# canayaz2560mega.net
KiCad netlist of a schematic drawn in EAGLE
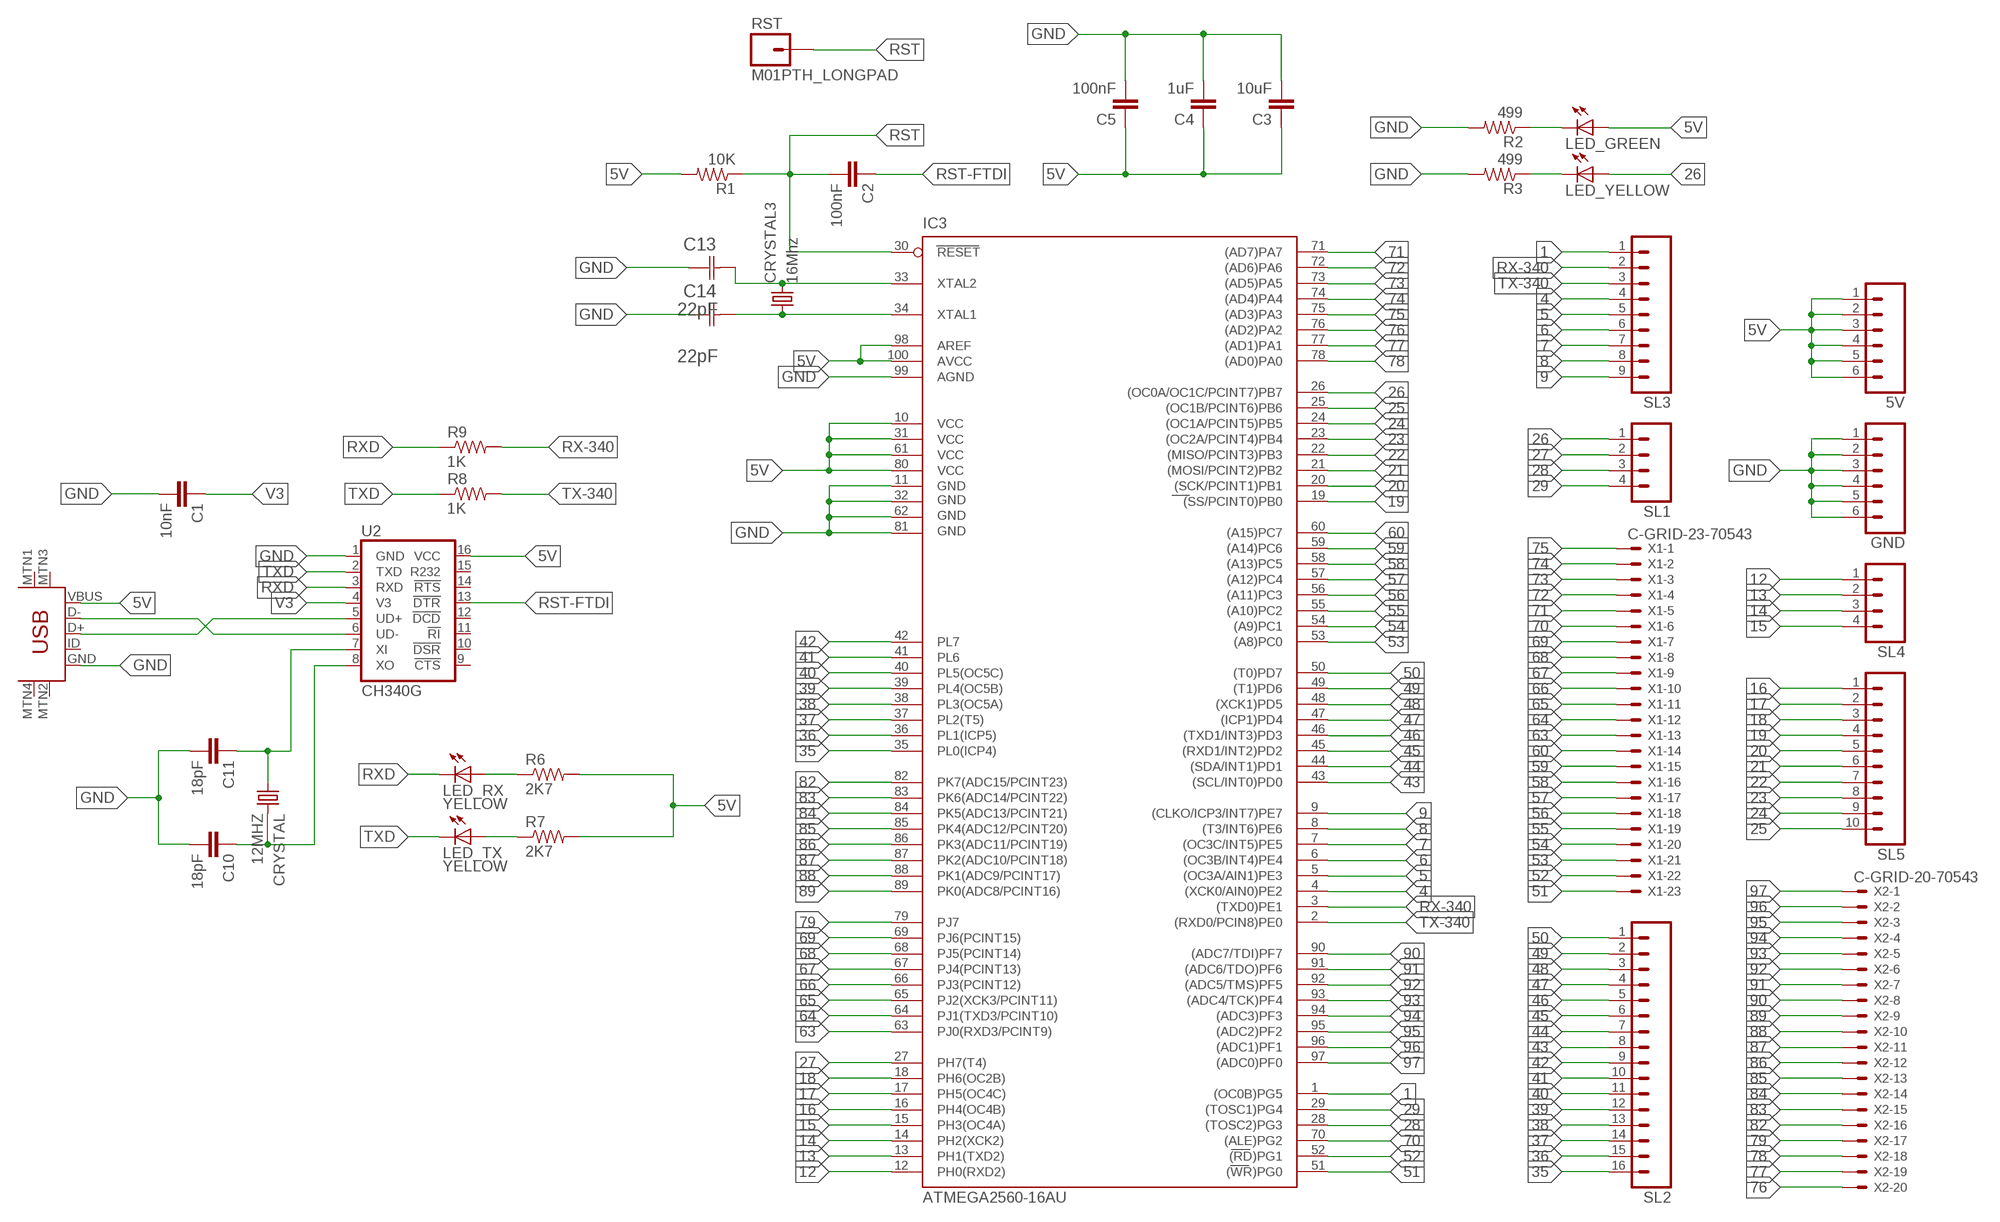
[diagram p0: schematic, sheet 1]

(export (version "E")
  (design (tool "Eeschema 10.0.6"))
  (components
    (comp (ref "5V")
      (value "M06")
      (footprint "eagle-import:06P")
      (libsource (lib "eagle-import") (part "M06"))
    )
    (comp (ref "C1")
      (value "10nF")
      (footprint "eagle-import:1206")
      (libsource (lib "eagle-import") (part "CAP1206"))
    )
    (comp (ref "C2")
      (value "100nF")
      (footprint "eagle-import:1206")
      (libsource (lib "eagle-import") (part "CAP1206"))
    )
    (comp (ref "C3")
      (value "10uF")
      (footprint "eagle-import:1206")
      (libsource (lib "eagle-import") (part "CAP1206"))
    )
    (comp (ref "C4")
      (value "1uF")
      (footprint "eagle-import:1206")
      (libsource (lib "eagle-import") (part "CAP1206"))
    )
    (comp (ref "C5")
      (value "100nF")
      (footprint "eagle-import:1206")
      (libsource (lib "eagle-import") (part "CAP1206"))
    )
    (comp (ref "C10")
      (value "18pF")
      (footprint "eagle-import:1206")
      (libsource (lib "eagle-import") (part "CAP1206"))
    )
    (comp (ref "C11")
      (value "18pF")
      (footprint "eagle-import:1206")
      (libsource (lib "eagle-import") (part "CAP1206"))
    )
    (comp (ref "C13")
      (value "22pF")
      (footprint "eagle-import:CAPC3216X178N")
      (fields (field (name "MPN") "0612ZC225MAT2A") (field (name "TOLERANCE") "±20%"))
      (libsource (lib "eagle-import") (part "0612ZC225MAT2A"))
    )
    (comp (ref "C14")
      (value "22pF")
      (footprint "eagle-import:CAPC3216X178N")
      (fields (field (name "MPN") "0612ZC225MAT2A") (field (name "TOLERANCE") "±20%"))
      (libsource (lib "eagle-import") (part "0612ZC225MAT2A"))
    )
    (comp (ref "CRYSTAL")
      (value "12MHZ")
      (footprint "eagle-import:CSM-7X-DU")
      (libsource (lib "eagle-import") (part "flight_controller.lbr01_FAB_Hello_CSM-7X-DU"))
    )
    (comp (ref "CRYSTAL3")
      (value "16Mhz")
      (footprint "eagle-import:CSM-7X-DU")
      (libsource (lib "eagle-import") (part "CSM-7X-DU"))
    )
    (comp (ref "GND")
      (value "M06")
      (footprint "eagle-import:06P")
      (libsource (lib "eagle-import") (part "M06"))
    )
    (comp (ref "IC3")
      (value "ATMEGA2560-16AU")
      (footprint "eagle-import:TQFP100")
      (libsource (lib "eagle-import") (part "ATMEGAAU1280-16"))
    )
    (comp (ref "LED_GREEN")
      (value "LED1206")
      (footprint "eagle-import:1206")
      (libsource (lib "eagle-import") (part "LED1206"))
    )
    (comp (ref "LED_RX")
      (value "YELLOW")
      (footprint "eagle-import:LED1206")
      (libsource (lib "eagle-import") (part "LED"))
    )
    (comp (ref "LED_TX")
      (value "YELLOW")
      (footprint "eagle-import:LED1206")
      (libsource (lib "eagle-import") (part "LED"))
    )
    (comp (ref "LED_YELLOW")
      (value "LED1206")
      (footprint "eagle-import:1206")
      (libsource (lib "eagle-import") (part "LED1206"))
    )
    (comp (ref "R1")
      (value "10K")
      (footprint "eagle-import:R1206")
      (libsource (lib "eagle-import") (part "RES-US1206"))
    )
    (comp (ref "R2")
      (value "499")
      (footprint "eagle-import:1206")
      (libsource (lib "eagle-import") (part "RESISTOR1206"))
    )
    (comp (ref "R3")
      (value "499")
      (footprint "eagle-import:1206")
      (libsource (lib "eagle-import") (part "RESISTOR1206"))
    )
    (comp (ref "R6")
      (value "2K7")
      (footprint "eagle-import:R1206")
      (libsource (lib "eagle-import") (part "RES-US1206"))
    )
    (comp (ref "R7")
      (value "2K7")
      (footprint "eagle-import:R1206")
      (libsource (lib "eagle-import") (part "RES-US1206"))
    )
    (comp (ref "R8")
      (value "1K")
      (footprint "eagle-import:R1206")
      (libsource (lib "eagle-import") (part "RES-US1206"))
    )
    (comp (ref "R9")
      (value "1K")
      (footprint "eagle-import:R1206")
      (libsource (lib "eagle-import") (part "RES-US1206"))
    )
    (comp (ref "RST")
      (value "M01PTH_LONGPAD")
      (footprint "eagle-import:1X01_LONGPAD")
      (libsource (lib "eagle-import") (part "M01PTH_LONGPAD"))
    )
    (comp (ref "SL1")
      (value "M04")
      (footprint "eagle-import:04P")
      (libsource (lib "eagle-import") (part "M04"))
    )
    (comp (ref "SL2")
      (value "M16")
      (footprint "eagle-import:16P")
      (libsource (lib "eagle-import") (part "M16"))
    )
    (comp (ref "SL3")
      (value "M09")
      (footprint "eagle-import:09P")
      (libsource (lib "eagle-import") (part "M09"))
    )
    (comp (ref "SL4")
      (value "M04")
      (footprint "eagle-import:04P")
      (libsource (lib "eagle-import") (part "M04"))
    )
    (comp (ref "SL5")
      (value "M10")
      (footprint "eagle-import:10P")
      (libsource (lib "eagle-import") (part "M10"))
    )
    (comp (ref "U$7")
      (value "USB-MINIB-5PIN")
      (footprint "eagle-import:USB-MINIB")
      (libsource (lib "eagle-import") (part "USB-MINIB-5PIN"))
    )
    (comp (ref "U2")
      (value "CH340G")
      (footprint "eagle-import:SO016")
      (libsource (lib "eagle-import") (part "CH340GSMD"))
    )
    (comp (ref "X1")
      (value "C-GRID-23-70543")
      (footprint "eagle-import:70543-23")
      (libsource (lib "eagle-import") (part "C-GRID-23-70543"))
    )
    (comp (ref "X2")
      (value "C-GRID-20-70543")
      (footprint "eagle-import:70543-20")
      (libsource (lib "eagle-import") (part "C-GRID-20-70543"))
    )
  )
  (nets
    (net (code "1") (name "1") (class "Default")
      (node (ref "IC3") (pin "1") (pinfunction "(OC0B)PG5_1") (pintype "bidirectional"))
      (node (ref "SL3") (pin "1") (pinfunction "1_1") (pintype "passive"))
    )
    (net (code "2") (name "4") (class "Default")
      (node (ref "IC3") (pin "4") (pinfunction "(XCK0/AIN0)PE2_4") (pintype "bidirectional"))
      (node (ref "SL3") (pin "4") (pinfunction "4_4") (pintype "passive"))
    )
    (net (code "3") (name "5") (class "Default")
      (node (ref "IC3") (pin "5") (pinfunction "(OC3A/AIN1)PE3_5") (pintype "bidirectional"))
      (node (ref "SL3") (pin "5") (pinfunction "5_5") (pintype "passive"))
    )
    (net (code "4") (name "5V") (class "Default")
      (node (ref "5V") (pin "1") (pinfunction "1_1") (pintype "passive"))
      (node (ref "5V") (pin "2") (pinfunction "2_2") (pintype "passive"))
      (node (ref "5V") (pin "3") (pinfunction "3_3") (pintype "passive"))
      (node (ref "5V") (pin "4") (pinfunction "4_4") (pintype "passive"))
      (node (ref "5V") (pin "5") (pinfunction "5_5") (pintype "passive"))
      (node (ref "5V") (pin "6") (pinfunction "6_6") (pintype "passive"))
      (node (ref "C3") (pin "1") (pinfunction "1_1") (pintype "passive"))
      (node (ref "C4") (pin "1") (pinfunction "1_1") (pintype "passive"))
      (node (ref "C5") (pin "1") (pinfunction "1_1") (pintype "passive"))
      (node (ref "IC3") (pin "10") (pinfunction "VCC_10") (pintype "power_in"))
      (node (ref "IC3") (pin "100") (pinfunction "AVCC_100") (pintype "power_in"))
      (node (ref "IC3") (pin "31") (pinfunction "VCC1_31") (pintype "power_in"))
      (node (ref "IC3") (pin "61") (pinfunction "VCC2_61") (pintype "power_in"))
      (node (ref "IC3") (pin "80") (pinfunction "VCC3_80") (pintype "power_in"))
      (node (ref "IC3") (pin "98") (pinfunction "AREF_98") (pintype "bidirectional"))
      (node (ref "LED_GREEN") (pin "1") (pinfunction "A_1") (pintype "passive"))
      (node (ref "R1") (pin "2") (pinfunction "2_2") (pintype "passive"))
      (node (ref "R6") (pin "2") (pinfunction "2_2") (pintype "passive"))
      (node (ref "R7") (pin "2") (pinfunction "2_2") (pintype "passive"))
      (node (ref "U$7") (pin "VBUS") (pinfunction "VBUS_VBUS") (pintype "bidirectional"))
      (node (ref "U2") (pin "16") (pinfunction "VCC_16") (pintype "bidirectional"))
    )
    (net (code "5") (name "6") (class "Default")
      (node (ref "IC3") (pin "6") (pinfunction "(OC3B/INT4)PE4_6") (pintype "bidirectional"))
      (node (ref "SL3") (pin "6") (pinfunction "6_6") (pintype "passive"))
    )
    (net (code "6") (name "7") (class "Default")
      (node (ref "IC3") (pin "7") (pinfunction "(OC3C/INT5)PE5_7") (pintype "bidirectional"))
      (node (ref "SL3") (pin "7") (pinfunction "7_7") (pintype "passive"))
    )
    (net (code "7") (name "8") (class "Default")
      (node (ref "IC3") (pin "8") (pinfunction "(T3/INT6)PE6_8") (pintype "bidirectional"))
      (node (ref "SL3") (pin "8") (pinfunction "8_8") (pintype "passive"))
    )
    (net (code "8") (name "9") (class "Default")
      (node (ref "IC3") (pin "9") (pinfunction "(CLKO/ICP3/INT7)PE7_9") (pintype "bidirectional"))
      (node (ref "SL3") (pin "9") (pinfunction "9_9") (pintype "passive"))
    )
    (net (code "9") (name "12") (class "Default")
      (node (ref "IC3") (pin "12") (pinfunction "PH0(RXD2)_12") (pintype "bidirectional"))
      (node (ref "SL4") (pin "1") (pinfunction "1_1") (pintype "passive"))
    )
    (net (code "10") (name "13") (class "Default")
      (node (ref "IC3") (pin "13") (pinfunction "PH1(TXD2)_13") (pintype "bidirectional"))
      (node (ref "SL4") (pin "2") (pinfunction "2_2") (pintype "passive"))
    )
    (net (code "11") (name "14") (class "Default")
      (node (ref "IC3") (pin "14") (pinfunction "PH2(XCK2)_14") (pintype "bidirectional"))
      (node (ref "SL4") (pin "3") (pinfunction "3_3") (pintype "passive"))
    )
    (net (code "12") (name "15") (class "Default")
      (node (ref "IC3") (pin "15") (pinfunction "PH3(OC4A)_15") (pintype "bidirectional"))
      (node (ref "SL4") (pin "4") (pinfunction "4_4") (pintype "passive"))
    )
    (net (code "13") (name "16") (class "Default")
      (node (ref "IC3") (pin "16") (pinfunction "PH4(OC4B)_16") (pintype "bidirectional"))
      (node (ref "SL5") (pin "1") (pinfunction "1_1") (pintype "passive"))
    )
    (net (code "14") (name "17") (class "Default")
      (node (ref "IC3") (pin "17") (pinfunction "PH5(OC4C)_17") (pintype "bidirectional"))
      (node (ref "SL5") (pin "2") (pinfunction "2_2") (pintype "passive"))
    )
    (net (code "15") (name "18") (class "Default")
      (node (ref "IC3") (pin "18") (pinfunction "PH6(OC2B)_18") (pintype "bidirectional"))
      (node (ref "SL5") (pin "3") (pinfunction "3_3") (pintype "passive"))
    )
    (net (code "16") (name "19") (class "Default")
      (node (ref "IC3") (pin "19") (pinfunction "(SS/PCINT0)PB0_19") (pintype "bidirectional"))
      (node (ref "SL5") (pin "4") (pinfunction "4_4") (pintype "passive"))
    )
    (net (code "17") (name "20") (class "Default")
      (node (ref "IC3") (pin "20") (pinfunction "(SCK/PCINT1)PB1_20") (pintype "bidirectional"))
      (node (ref "SL5") (pin "5") (pinfunction "5_5") (pintype "passive"))
    )
    (net (code "18") (name "21") (class "Default")
      (node (ref "IC3") (pin "21") (pinfunction "(MOSI/PCINT2)PB2_21") (pintype "bidirectional"))
      (node (ref "SL5") (pin "6") (pinfunction "6_6") (pintype "passive"))
    )
    (net (code "19") (name "22") (class "Default")
      (node (ref "IC3") (pin "22") (pinfunction "(MISO/PCINT3)PB3_22") (pintype "bidirectional"))
      (node (ref "SL5") (pin "7") (pinfunction "7_7") (pintype "passive"))
    )
    (net (code "20") (name "23") (class "Default")
      (node (ref "IC3") (pin "23") (pinfunction "(OC2A/PCINT4)PB4_23") (pintype "bidirectional"))
      (node (ref "SL5") (pin "8") (pinfunction "8_8") (pintype "passive"))
    )
    (net (code "21") (name "24") (class "Default")
      (node (ref "IC3") (pin "24") (pinfunction "(OC1A/PCINT5)PB5_24") (pintype "bidirectional"))
      (node (ref "SL5") (pin "9") (pinfunction "9_9") (pintype "passive"))
    )
    (net (code "22") (name "25") (class "Default")
      (node (ref "IC3") (pin "25") (pinfunction "(OC1B/PCINT6)PB6_25") (pintype "bidirectional"))
      (node (ref "SL5") (pin "10") (pinfunction "10_10") (pintype "passive"))
    )
    (net (code "23") (name "26") (class "Default")
      (node (ref "IC3") (pin "26") (pinfunction "(OC0A/OC1C/PCINT7)PB7_26") (pintype "bidirectional"))
      (node (ref "LED_YELLOW") (pin "1") (pinfunction "A_1") (pintype "passive"))
      (node (ref "SL1") (pin "1") (pinfunction "1_1") (pintype "passive"))
    )
    (net (code "24") (name "27") (class "Default")
      (node (ref "IC3") (pin "27") (pinfunction "PH7(T4)_27") (pintype "bidirectional"))
      (node (ref "SL1") (pin "2") (pinfunction "2_2") (pintype "passive"))
    )
    (net (code "25") (name "28") (class "Default")
      (node (ref "IC3") (pin "28") (pinfunction "(TOSC2)PG3_28") (pintype "bidirectional"))
      (node (ref "SL1") (pin "3") (pinfunction "3_3") (pintype "passive"))
    )
    (net (code "26") (name "29") (class "Default")
      (node (ref "IC3") (pin "29") (pinfunction "(TOSC1)PG4_29") (pintype "bidirectional"))
      (node (ref "SL1") (pin "4") (pinfunction "4_4") (pintype "passive"))
    )
    (net (code "27") (name "35") (class "Default")
      (node (ref "IC3") (pin "35") (pinfunction "PL0(ICP4)_35") (pintype "bidirectional"))
      (node (ref "SL2") (pin "16") (pinfunction "16_16") (pintype "passive"))
    )
    (net (code "28") (name "36") (class "Default")
      (node (ref "IC3") (pin "36") (pinfunction "PL1(ICP5)_36") (pintype "bidirectional"))
      (node (ref "SL2") (pin "15") (pinfunction "15_15") (pintype "passive"))
    )
    (net (code "29") (name "37") (class "Default")
      (node (ref "IC3") (pin "37") (pinfunction "PL2(T5)_37") (pintype "bidirectional"))
      (node (ref "SL2") (pin "14") (pinfunction "14_14") (pintype "passive"))
    )
    (net (code "30") (name "38") (class "Default")
      (node (ref "IC3") (pin "38") (pinfunction "PL3(OC5A)_38") (pintype "bidirectional"))
      (node (ref "SL2") (pin "13") (pinfunction "13_13") (pintype "passive"))
    )
    (net (code "31") (name "39") (class "Default")
      (node (ref "IC3") (pin "39") (pinfunction "PL4(OC5B)_39") (pintype "bidirectional"))
      (node (ref "SL2") (pin "12") (pinfunction "12_12") (pintype "passive"))
    )
    (net (code "32") (name "40") (class "Default")
      (node (ref "IC3") (pin "40") (pinfunction "PL5(OC5C)_40") (pintype "bidirectional"))
      (node (ref "SL2") (pin "11") (pinfunction "11_11") (pintype "passive"))
    )
    (net (code "33") (name "41") (class "Default")
      (node (ref "IC3") (pin "41") (pinfunction "PL6_41") (pintype "bidirectional"))
      (node (ref "SL2") (pin "10") (pinfunction "10_10") (pintype "passive"))
    )
    (net (code "34") (name "42") (class "Default")
      (node (ref "IC3") (pin "42") (pinfunction "PL7_42") (pintype "bidirectional"))
      (node (ref "SL2") (pin "9") (pinfunction "9_9") (pintype "passive"))
    )
    (net (code "35") (name "43") (class "Default")
      (node (ref "IC3") (pin "43") (pinfunction "(SCL/INT0)PD0_43") (pintype "bidirectional"))
      (node (ref "SL2") (pin "8") (pinfunction "8_8") (pintype "passive"))
    )
    (net (code "36") (name "44") (class "Default")
      (node (ref "IC3") (pin "44") (pinfunction "(SDA/INT1)PD1_44") (pintype "bidirectional"))
      (node (ref "SL2") (pin "7") (pinfunction "7_7") (pintype "passive"))
    )
    (net (code "37") (name "45") (class "Default")
      (node (ref "IC3") (pin "45") (pinfunction "(RXD1/INT2)PD2_45") (pintype "bidirectional"))
      (node (ref "SL2") (pin "6") (pinfunction "6_6") (pintype "passive"))
    )
    (net (code "38") (name "46") (class "Default")
      (node (ref "IC3") (pin "46") (pinfunction "(TXD1/INT3)PD3_46") (pintype "bidirectional"))
      (node (ref "SL2") (pin "5") (pinfunction "5_5") (pintype "passive"))
    )
    (net (code "39") (name "47") (class "Default")
      (node (ref "IC3") (pin "47") (pinfunction "(ICP1)PD4_47") (pintype "bidirectional"))
      (node (ref "SL2") (pin "4") (pinfunction "4_4") (pintype "passive"))
    )
    (net (code "40") (name "48") (class "Default")
      (node (ref "IC3") (pin "48") (pinfunction "(XCK1)PD5_48") (pintype "bidirectional"))
      (node (ref "SL2") (pin "3") (pinfunction "3_3") (pintype "passive"))
    )
    (net (code "41") (name "49") (class "Default")
      (node (ref "IC3") (pin "49") (pinfunction "(T1)PD6_49") (pintype "bidirectional"))
      (node (ref "SL2") (pin "2") (pinfunction "2_2") (pintype "passive"))
    )
    (net (code "42") (name "50") (class "Default")
      (node (ref "IC3") (pin "50") (pinfunction "(T0)PD7_50") (pintype "bidirectional"))
      (node (ref "SL2") (pin "1") (pinfunction "1_1") (pintype "passive"))
    )
    (net (code "43") (name "51") (class "Default")
      (node (ref "IC3") (pin "51") (pinfunction "(WR)PG0_51") (pintype "bidirectional"))
      (node (ref "X1") (pin "23") (pinfunction "S_23") (pintype "passive"))
    )
    (net (code "44") (name "52") (class "Default")
      (node (ref "IC3") (pin "52") (pinfunction "(RD)PG1_52") (pintype "bidirectional"))
      (node (ref "X1") (pin "22") (pinfunction "S_22") (pintype "passive"))
    )
    (net (code "45") (name "53") (class "Default")
      (node (ref "IC3") (pin "53") (pinfunction "(A8)PC0_53") (pintype "bidirectional"))
      (node (ref "X1") (pin "21") (pinfunction "S_21") (pintype "passive"))
    )
    (net (code "46") (name "54") (class "Default")
      (node (ref "IC3") (pin "54") (pinfunction "(A9)PC1_54") (pintype "bidirectional"))
      (node (ref "X1") (pin "20") (pinfunction "S_20") (pintype "passive"))
    )
    (net (code "47") (name "55") (class "Default")
      (node (ref "IC3") (pin "55") (pinfunction "(A10)PC2_55") (pintype "bidirectional"))
      (node (ref "X1") (pin "19") (pinfunction "S_19") (pintype "passive"))
    )
    (net (code "48") (name "56") (class "Default")
      (node (ref "IC3") (pin "56") (pinfunction "(A11)PC3_56") (pintype "bidirectional"))
      (node (ref "X1") (pin "18") (pinfunction "S_18") (pintype "passive"))
    )
    (net (code "49") (name "57") (class "Default")
      (node (ref "IC3") (pin "57") (pinfunction "(A12)PC4_57") (pintype "bidirectional"))
      (node (ref "X1") (pin "17") (pinfunction "S_17") (pintype "passive"))
    )
    (net (code "50") (name "58") (class "Default")
      (node (ref "IC3") (pin "58") (pinfunction "(A13)PC5_58") (pintype "bidirectional"))
      (node (ref "X1") (pin "16") (pinfunction "S_16") (pintype "passive"))
    )
    (net (code "51") (name "59") (class "Default")
      (node (ref "IC3") (pin "59") (pinfunction "(A14)PC6_59") (pintype "bidirectional"))
      (node (ref "X1") (pin "15") (pinfunction "S_15") (pintype "passive"))
    )
    (net (code "52") (name "60") (class "Default")
      (node (ref "IC3") (pin "60") (pinfunction "(A15)PC7_60") (pintype "bidirectional"))
      (node (ref "X1") (pin "14") (pinfunction "S_14") (pintype "passive"))
    )
    (net (code "53") (name "63") (class "Default")
      (node (ref "IC3") (pin "63") (pinfunction "PJ0(RXD3/PCINT9)_63") (pintype "bidirectional"))
      (node (ref "X1") (pin "13") (pinfunction "S_13") (pintype "passive"))
    )
    (net (code "54") (name "64") (class "Default")
      (node (ref "IC3") (pin "64") (pinfunction "PJ1(TXD3/PCINT10)_64") (pintype "bidirectional"))
      (node (ref "X1") (pin "12") (pinfunction "S_12") (pintype "passive"))
    )
    (net (code "55") (name "65") (class "Default")
      (node (ref "IC3") (pin "65") (pinfunction "PJ2(XCK3/PCINT11)_65") (pintype "bidirectional"))
      (node (ref "X1") (pin "11") (pinfunction "S_11") (pintype "passive"))
    )
    (net (code "56") (name "66") (class "Default")
      (node (ref "IC3") (pin "66") (pinfunction "PJ3(PCINT12)_66") (pintype "bidirectional"))
      (node (ref "X1") (pin "10") (pinfunction "S_10") (pintype "passive"))
    )
    (net (code "57") (name "67") (class "Default")
      (node (ref "IC3") (pin "67") (pinfunction "PJ4(PCINT13)_67") (pintype "bidirectional"))
      (node (ref "X1") (pin "9") (pinfunction "S_9") (pintype "passive"))
    )
    (net (code "58") (name "68") (class "Default")
      (node (ref "IC3") (pin "68") (pinfunction "PJ5(PCINT14)_68") (pintype "bidirectional"))
      (node (ref "X1") (pin "8") (pinfunction "S_8") (pintype "passive"))
    )
    (net (code "59") (name "69") (class "Default")
      (node (ref "IC3") (pin "69") (pinfunction "PJ6(PCINT15)_69") (pintype "bidirectional"))
      (node (ref "X1") (pin "7") (pinfunction "S_7") (pintype "passive"))
    )
    (net (code "60") (name "70") (class "Default")
      (node (ref "IC3") (pin "70") (pinfunction "(ALE)PG2_70") (pintype "bidirectional"))
      (node (ref "X1") (pin "6") (pinfunction "S_6") (pintype "passive"))
    )
    (net (code "61") (name "71") (class "Default")
      (node (ref "IC3") (pin "71") (pinfunction "(AD7)PA7_71") (pintype "bidirectional"))
      (node (ref "X1") (pin "5") (pinfunction "S_5") (pintype "passive"))
    )
    (net (code "62") (name "72") (class "Default")
      (node (ref "IC3") (pin "72") (pinfunction "(AD6)PA6_72") (pintype "bidirectional"))
      (node (ref "X1") (pin "4") (pinfunction "S_4") (pintype "passive"))
    )
    (net (code "63") (name "73") (class "Default")
      (node (ref "IC3") (pin "73") (pinfunction "(AD5)PA5_73") (pintype "bidirectional"))
      (node (ref "X1") (pin "3") (pinfunction "S_3") (pintype "passive"))
    )
    (net (code "64") (name "74") (class "Default")
      (node (ref "IC3") (pin "74") (pinfunction "(AD4)PA4_74") (pintype "bidirectional"))
      (node (ref "X1") (pin "2") (pinfunction "S_2") (pintype "passive"))
    )
    (net (code "65") (name "75") (class "Default")
      (node (ref "IC3") (pin "75") (pinfunction "(AD3)PA3_75") (pintype "bidirectional"))
      (node (ref "X1") (pin "1") (pinfunction "S_1") (pintype "passive"))
    )
    (net (code "66") (name "76") (class "Default")
      (node (ref "IC3") (pin "76") (pinfunction "(AD2)PA2_76") (pintype "bidirectional"))
      (node (ref "X2") (pin "20") (pinfunction "S_20") (pintype "passive"))
    )
    (net (code "67") (name "77") (class "Default")
      (node (ref "IC3") (pin "77") (pinfunction "(AD1)PA1_77") (pintype "bidirectional"))
      (node (ref "X2") (pin "19") (pinfunction "S_19") (pintype "passive"))
    )
    (net (code "68") (name "78") (class "Default")
      (node (ref "IC3") (pin "78") (pinfunction "(AD0)PA0_78") (pintype "bidirectional"))
      (node (ref "X2") (pin "18") (pinfunction "S_18") (pintype "passive"))
    )
    (net (code "69") (name "79") (class "Default")
      (node (ref "IC3") (pin "79") (pinfunction "PJ7_79") (pintype "bidirectional"))
      (node (ref "X2") (pin "17") (pinfunction "S_17") (pintype "passive"))
    )
    (net (code "70") (name "82") (class "Default")
      (node (ref "IC3") (pin "82") (pinfunction "PK7(ADC15/PCINT23)_82") (pintype "bidirectional"))
      (node (ref "X2") (pin "16") (pinfunction "S_16") (pintype "passive"))
    )
    (net (code "71") (name "83") (class "Default")
      (node (ref "IC3") (pin "83") (pinfunction "PK6(ADC14/PCINT22)_83") (pintype "bidirectional"))
      (node (ref "X2") (pin "15") (pinfunction "S_15") (pintype "passive"))
    )
    (net (code "72") (name "84") (class "Default")
      (node (ref "IC3") (pin "84") (pinfunction "PK5(ADC13/PCINT21)_84") (pintype "bidirectional"))
      (node (ref "X2") (pin "14") (pinfunction "S_14") (pintype "passive"))
    )
    (net (code "73") (name "85") (class "Default")
      (node (ref "IC3") (pin "85") (pinfunction "PK4(ADC12/PCINT20)_85") (pintype "bidirectional"))
      (node (ref "X2") (pin "13") (pinfunction "S_13") (pintype "passive"))
    )
    (net (code "74") (name "86") (class "Default")
      (node (ref "IC3") (pin "86") (pinfunction "PK3(ADC11/PCINT19)_86") (pintype "bidirectional"))
      (node (ref "X2") (pin "12") (pinfunction "S_12") (pintype "passive"))
    )
    (net (code "75") (name "87") (class "Default")
      (node (ref "IC3") (pin "87") (pinfunction "PK2(ADC10/PCINT18)_87") (pintype "bidirectional"))
      (node (ref "X2") (pin "11") (pinfunction "S_11") (pintype "passive"))
    )
    (net (code "76") (name "88") (class "Default")
      (node (ref "IC3") (pin "88") (pinfunction "PK1(ADC9/PCINT17)_88") (pintype "bidirectional"))
      (node (ref "X2") (pin "10") (pinfunction "S_10") (pintype "passive"))
    )
    (net (code "77") (name "89") (class "Default")
      (node (ref "IC3") (pin "89") (pinfunction "PK0(ADC8/PCINT16)_89") (pintype "bidirectional"))
      (node (ref "X2") (pin "9") (pinfunction "S_9") (pintype "passive"))
    )
    (net (code "78") (name "90") (class "Default")
      (node (ref "IC3") (pin "90") (pinfunction "(ADC7/TDI)PF7_90") (pintype "bidirectional"))
      (node (ref "X2") (pin "8") (pinfunction "S_8") (pintype "passive"))
    )
    (net (code "79") (name "91") (class "Default")
      (node (ref "IC3") (pin "91") (pinfunction "(ADC6/TDO)PF6_91") (pintype "bidirectional"))
      (node (ref "X2") (pin "7") (pinfunction "S_7") (pintype "passive"))
    )
    (net (code "80") (name "92") (class "Default")
      (node (ref "IC3") (pin "92") (pinfunction "(ADC5/TMS)PF5_92") (pintype "bidirectional"))
      (node (ref "X2") (pin "6") (pinfunction "S_6") (pintype "passive"))
    )
    (net (code "81") (name "93") (class "Default")
      (node (ref "IC3") (pin "93") (pinfunction "(ADC4/TCK)PF4_93") (pintype "bidirectional"))
      (node (ref "X2") (pin "5") (pinfunction "S_5") (pintype "passive"))
    )
    (net (code "82") (name "94") (class "Default")
      (node (ref "IC3") (pin "94") (pinfunction "(ADC3)PF3_94") (pintype "bidirectional"))
      (node (ref "X2") (pin "4") (pinfunction "S_4") (pintype "passive"))
    )
    (net (code "83") (name "95") (class "Default")
      (node (ref "IC3") (pin "95") (pinfunction "(ADC2)PF2_95") (pintype "bidirectional"))
      (node (ref "X2") (pin "3") (pinfunction "S_3") (pintype "passive"))
    )
    (net (code "84") (name "96") (class "Default")
      (node (ref "IC3") (pin "96") (pinfunction "(ADC1)PF1_96") (pintype "bidirectional"))
      (node (ref "X2") (pin "2") (pinfunction "S_2") (pintype "passive"))
    )
    (net (code "85") (name "97") (class "Default")
      (node (ref "IC3") (pin "97") (pinfunction "(ADC0)PF0_97") (pintype "bidirectional"))
      (node (ref "X2") (pin "1") (pinfunction "S_1") (pintype "passive"))
    )
    (net (code "86") (name "GND") (class "Default")
      (node (ref "C1") (pin "2") (pinfunction "2_2") (pintype "passive"))
      (node (ref "C10") (pin "2") (pinfunction "2_2") (pintype "passive"))
      (node (ref "C11") (pin "2") (pinfunction "2_2") (pintype "passive"))
      (node (ref "C13") (pin "1") (pinfunction "C1_1") (pintype "passive"))
      (node (ref "C14") (pin "1") (pinfunction "C1_1") (pintype "passive"))
      (node (ref "C3") (pin "2") (pinfunction "2_2") (pintype "passive"))
      (node (ref "C4") (pin "2") (pinfunction "2_2") (pintype "passive"))
      (node (ref "C5") (pin "2") (pinfunction "2_2") (pintype "passive"))
      (node (ref "GND") (pin "1") (pinfunction "1_1") (pintype "passive"))
      (node (ref "GND") (pin "2") (pinfunction "2_2") (pintype "passive"))
      (node (ref "GND") (pin "3") (pinfunction "3_3") (pintype "passive"))
      (node (ref "GND") (pin "4") (pinfunction "4_4") (pintype "passive"))
      (node (ref "GND") (pin "5") (pinfunction "5_5") (pintype "passive"))
      (node (ref "GND") (pin "6") (pinfunction "6_6") (pintype "passive"))
      (node (ref "IC3") (pin "11") (pinfunction "GND_11") (pintype "power_in"))
      (node (ref "IC3") (pin "32") (pinfunction "GND1_32") (pintype "power_in"))
      (node (ref "IC3") (pin "62") (pinfunction "GND2_62") (pintype "power_in"))
      (node (ref "IC3") (pin "81") (pinfunction "GND3_81") (pintype "power_in"))
      (node (ref "IC3") (pin "99") (pinfunction "AGND_99") (pintype "power_in"))
      (node (ref "R2") (pin "2") (pinfunction "2_2") (pintype "passive"))
      (node (ref "R3") (pin "2") (pinfunction "2_2") (pintype "passive"))
      (node (ref "U$7") (pin "GND") (pinfunction "GND_GND") (pintype "bidirectional"))
      (node (ref "U2") (pin "1") (pinfunction "GND_1") (pintype "bidirectional"))
    )
    (net (code "87") (name "Net-(C13-C2)") (class "Default")
      (node (ref "C13") (pin "2") (pinfunction "C2_2") (pintype "passive"))
      (node (ref "CRYSTAL3") (pin "2") (pinfunction "2_2") (pintype "passive"))
      (node (ref "IC3") (pin "33") (pinfunction "XTAL2_33") (pintype "output"))
    )
    (net (code "88") (name "Net-(C14-C2)") (class "Default")
      (node (ref "C14") (pin "2") (pinfunction "C2_2") (pintype "passive"))
      (node (ref "CRYSTAL3") (pin "1") (pinfunction "1_1") (pintype "passive"))
      (node (ref "IC3") (pin "34") (pinfunction "XTAL1_34") (pintype "input"))
    )
    (net (code "89") (name "Net-(LED_GREEN-C)") (class "Default")
      (node (ref "LED_GREEN") (pin "2") (pinfunction "C_2") (pintype "passive"))
      (node (ref "R2") (pin "1") (pinfunction "1_1") (pintype "passive"))
    )
    (net (code "90") (name "Net-(LED_RX-A)") (class "Default")
      (node (ref "LED_RX") (pin "1") (pinfunction "A_1") (pintype "passive"))
      (node (ref "R6") (pin "1") (pinfunction "1_1") (pintype "passive"))
    )
    (net (code "91") (name "Net-(LED_TX-A)") (class "Default")
      (node (ref "LED_TX") (pin "1") (pinfunction "A_1") (pintype "passive"))
      (node (ref "R7") (pin "1") (pinfunction "1_1") (pintype "passive"))
    )
    (net (code "92") (name "Net-(LED_YELLOW-C)") (class "Default")
      (node (ref "LED_YELLOW") (pin "2") (pinfunction "C_2") (pintype "passive"))
      (node (ref "R3") (pin "1") (pinfunction "1_1") (pintype "passive"))
    )
    (net (code "93") (name "Net-(U2-UD+)") (class "Default")
      (node (ref "U$7") (pin "D+") (pinfunction "D+_D+") (pintype "bidirectional"))
      (node (ref "U2") (pin "5") (pinfunction "UD+_5") (pintype "bidirectional"))
    )
    (net (code "94") (name "Net-(U2-UD-)") (class "Default")
      (node (ref "U$7") (pin "D-") (pinfunction "D-_D-") (pintype "bidirectional"))
      (node (ref "U2") (pin "6") (pinfunction "UD-_6") (pintype "bidirectional"))
    )
    (net (code "95") (name "Net-(U2-XI)") (class "Default")
      (node (ref "C11") (pin "1") (pinfunction "1_1") (pintype "passive"))
      (node (ref "CRYSTAL") (pin "1") (pinfunction "1_1") (pintype "passive"))
      (node (ref "U2") (pin "7") (pinfunction "XI_7") (pintype "bidirectional"))
    )
    (net (code "96") (name "Net-(U2-XO)") (class "Default")
      (node (ref "C10") (pin "1") (pinfunction "1_1") (pintype "passive"))
      (node (ref "CRYSTAL") (pin "2") (pinfunction "2_2") (pintype "passive"))
      (node (ref "U2") (pin "8") (pinfunction "XO_8") (pintype "bidirectional"))
    )
    (net (code "97") (name "RST") (class "Default")
      (node (ref "C2") (pin "2") (pinfunction "2_2") (pintype "passive"))
      (node (ref "IC3") (pin "30") (pinfunction "RESET_30") (pintype "input"))
      (node (ref "R1") (pin "1") (pinfunction "1_1") (pintype "passive"))
      (node (ref "RST") (pin "1") (pinfunction "1_1") (pintype "passive"))
    )
    (net (code "98") (name "RST-FTDI") (class "Default")
      (node (ref "C2") (pin "1") (pinfunction "1_1") (pintype "passive"))
      (node (ref "U2") (pin "13") (pinfunction "~{DTR}_13") (pintype "bidirectional"))
    )
    (net (code "99") (name "RX-340") (class "Default")
      (node (ref "IC3") (pin "3") (pinfunction "(TXD0)PE1_3") (pintype "bidirectional"))
      (node (ref "R9") (pin "2") (pinfunction "2_2") (pintype "passive"))
      (node (ref "SL3") (pin "2") (pinfunction "2_2") (pintype "passive"))
    )
    (net (code "100") (name "RXD") (class "Default")
      (node (ref "LED_RX") (pin "2") (pinfunction "C_2") (pintype "passive"))
      (node (ref "R9") (pin "1") (pinfunction "1_1") (pintype "passive"))
      (node (ref "U2") (pin "3") (pinfunction "RXD_3") (pintype "bidirectional"))
    )
    (net (code "101") (name "TX-340") (class "Default")
      (node (ref "IC3") (pin "2") (pinfunction "(RXD0/PCIN8)PE0_2") (pintype "bidirectional"))
      (node (ref "R8") (pin "2") (pinfunction "2_2") (pintype "passive"))
      (node (ref "SL3") (pin "3") (pinfunction "3_3") (pintype "passive"))
    )
    (net (code "102") (name "TXD") (class "Default")
      (node (ref "LED_TX") (pin "2") (pinfunction "C_2") (pintype "passive"))
      (node (ref "R8") (pin "1") (pinfunction "1_1") (pintype "passive"))
      (node (ref "U2") (pin "2") (pinfunction "TXD_2") (pintype "bidirectional"))
    )
    (net (code "103") (name "V3") (class "Default")
      (node (ref "C1") (pin "1") (pinfunction "1_1") (pintype "passive"))
      (node (ref "U2") (pin "4") (pinfunction "V3_4") (pintype "bidirectional"))
    )
    (net (code "104") (name "unconnected-(U$7-MTN1-PadMTN3)") (class "Default")
      (node (ref "U$7") (pin "MTN3") (pinfunction "MTN1_MTN3") (pintype "bidirectional"))
    )
    (net (code "105") (name "unconnected-(U$7-MTN2-PadMTN1)") (class "Default")
      (node (ref "U$7") (pin "MTN1") (pinfunction "MTN2_MTN1") (pintype "bidirectional"))
    )
    (net (code "106") (name "unconnected-(U$7-MTN3-PadMTN2)") (class "Default")
      (node (ref "U$7") (pin "MTN2") (pinfunction "MTN3_MTN2") (pintype "bidirectional"))
    )
    (net (code "107") (name "unconnected-(U$7-PadID)") (class "Default")
      (node (ref "U$7") (pin "ID") (pinfunction "ID_ID") (pintype "bidirectional"))
    )
    (net (code "108") (name "unconnected-(U$7-PadMTN4)") (class "Default")
      (node (ref "U$7") (pin "MTN4") (pinfunction "MTN4_MTN4") (pintype "bidirectional"))
    )
    (net (code "109") (name "unconnected-(U2-R232-Pad15)") (class "Default")
      (node (ref "U2") (pin "15") (pinfunction "R232_15") (pintype "bidirectional"))
    )
    (net (code "110") (name "unconnected-(U2-~{CTS}-Pad9)") (class "Default")
      (node (ref "U2") (pin "9") (pinfunction "~{CTS}_9") (pintype "bidirectional"))
    )
    (net (code "111") (name "unconnected-(U2-~{DCD}-Pad12)") (class "Default")
      (node (ref "U2") (pin "12") (pinfunction "~{DCD}_12") (pintype "bidirectional"))
    )
    (net (code "112") (name "unconnected-(U2-~{DSR}-Pad10)") (class "Default")
      (node (ref "U2") (pin "10") (pinfunction "~{DSR}_10") (pintype "bidirectional"))
    )
    (net (code "113") (name "unconnected-(U2-~{RI}-Pad11)") (class "Default")
      (node (ref "U2") (pin "11") (pinfunction "~{RI}_11") (pintype "bidirectional"))
    )
    (net (code "114") (name "unconnected-(U2-~{RTS}-Pad14)") (class "Default")
      (node (ref "U2") (pin "14") (pinfunction "~{RTS}_14") (pintype "bidirectional"))
    )
  )
)
